# Microcontroller.net
KiCad netlist of a schematic drawn in Altium Designer
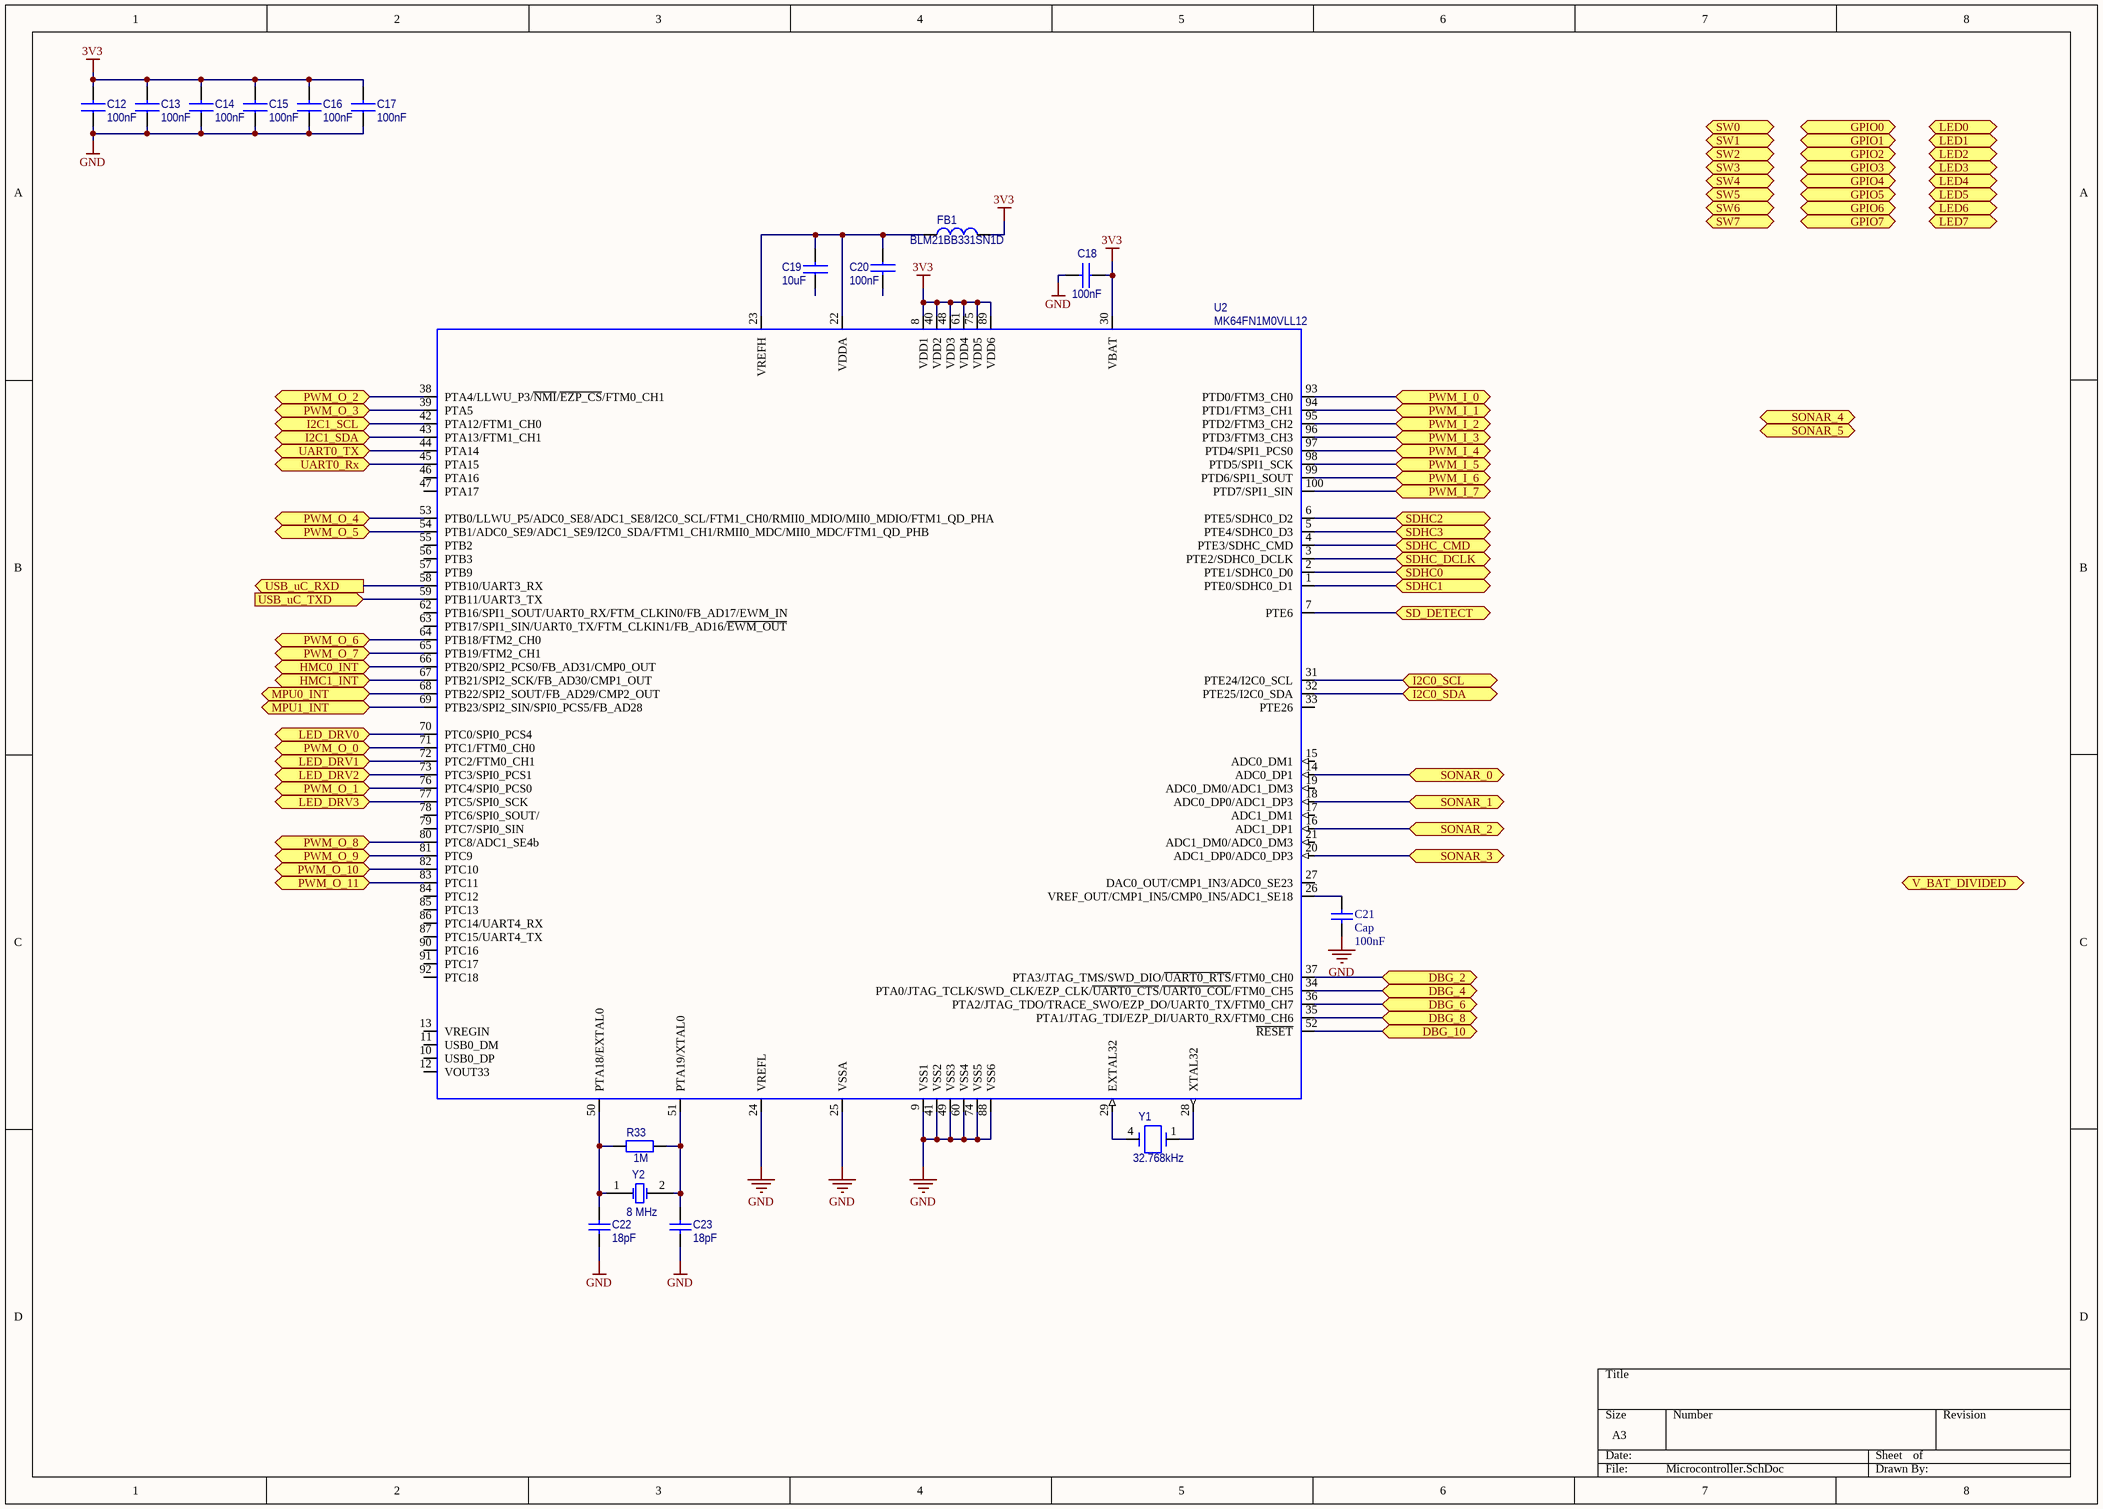
[diagram p0: Microcontroller.SchDoc]

(export (version "E")
  (design (tool "Eeschema 10.0.6"))
  (components
    (comp (ref "C12")
      (value "100nF")
      (footprint "060301")
      (description "CAP CER 0.1UF 25V 10% X7R 0603")
      (fields (field (name "VOLTAGE") "25V"))
      (libsource (lib "EISI") (part "CAPA"))
    )
    (comp (ref "C13")
      (value "100nF")
      (footprint "060301")
      (description "CAP CER 0.1UF 25V 10% X7R 0603")
      (fields (field (name "VOLTAGE") "25V"))
      (libsource (lib "EISI") (part "CAPA"))
    )
    (comp (ref "C14")
      (value "100nF")
      (footprint "060301")
      (description "CAP CER 0.1UF 25V 10% X7R 0603")
      (fields (field (name "VOLTAGE") "25V"))
      (libsource (lib "EISI") (part "CAPA"))
    )
    (comp (ref "C15")
      (value "100nF")
      (footprint "060301")
      (description "CAP CER 0.1UF 25V 10% X7R 0603")
      (fields (field (name "VOLTAGE") "25V"))
      (libsource (lib "EISI") (part "CAPA"))
    )
    (comp (ref "C16")
      (value "100nF")
      (footprint "060301")
      (description "CAP CER 0.1UF 25V 10% X7R 0603")
      (fields (field (name "VOLTAGE") "25V"))
      (libsource (lib "EISI") (part "CAPA"))
    )
    (comp (ref "C17")
      (value "100nF")
      (footprint "060301")
      (description "CAP CER 0.1UF 25V 10% X7R 0603")
      (fields (field (name "VOLTAGE") "25V"))
      (libsource (lib "EISI") (part "CAPA"))
    )
    (comp (ref "C18")
      (value "100nF")
      (footprint "060301")
      (description "CAP CER 0.1UF 25V 10% X7R 0603")
      (fields (field (name "VOLTAGE") "25V"))
      (libsource (lib "EISI") (part "CAPA"))
    )
    (comp (ref "C19")
      (value "10uF")
      (footprint "060301")
      (description "CAP CER 10UF 10V 10% X5R 0603")
      (fields (field (name "VOLTAGE") "10V") (field (name "Comment") "C1608X5R1A106K080AC"))
      (libsource (lib "EISI") (part "CAPA"))
    )
    (comp (ref "C20")
      (value "100nF")
      (footprint "060301")
      (description "CAP CER 0.1UF 25V 10% X7R 0603")
      (fields (field (name "VOLTAGE") "25V"))
      (libsource (lib "EISI") (part "CAPA"))
    )
    (comp (ref "C21")
      (value "Cap")
      (footprint "RAD-0.3")
      (description "Capacitor")
      (fields (field (name "ALTIUM_VALUE") "100nF") (field (name "PUBLISHER") "Altium Limited"))
      (libsource (lib "Miscellaneous Devices") (part "Cap"))
    )
    (comp (ref "C22")
      (value "18pF")
      (footprint "060301")
      (description "CAP CER 18PF 50V 5% NP0 0603")
      (libsource (lib "Miscellaneous Devices") (part "Cap Semi"))
    )
    (comp (ref "C23")
      (value "18pF")
      (footprint "060301")
      (description "CAP CER 18PF 50V 5% NP0 0603")
      (libsource (lib "Miscellaneous Devices") (part "Cap Semi"))
    )
    (comp (ref "FB1")
      (value "BLM21BB331SN1D")
      (footprint "080501")
      (description "EMI Filter Beads, Chips & Arrays 0805 330 OHM")
      (libsource (lib "EISI") (part "Ferrite Bead"))
    )
    (comp (ref "R33")
      (value "1M")
      (footprint "060301")
      (description "RES 1.00M OHM 1/10W 1% 0603 SMD")
      (libsource (lib "EISI") (part "RES"))
    )
    (comp (ref "U2")
      (value "MK64FN1M0VLL12")
      (description "IC MCU 1MB FLASH 120MHZ 1.71-3.6V LQFP100")
      (libsource (lib "SCH-28163-1") (part "K64FN1M0VLL12_100P"))
    )
    (comp (ref "Y1")
      (value "32.768kHz")
      (description "CRYSTAL 32.768 KHZ 12.5PF SMD")
      (fields (field (name "Comment") "ECS-.327-12.5-17X-C-TR"))
      (libsource (lib "*") (part "Crystal_32"))
    )
    (comp (ref "Y2")
      (value "8 MHz")
      (footprint "XT8_2-SMD")
      (description "CRYSTAL 8MHZ 18PF SMD")
      (fields (field (name "Comment") "ABM3-8.000MHZ-D2Y-T"))
      (libsource (lib "Miscellaneous Devices") (part "XTAL"))
    )
  )
  (nets
    (net (code "1") (name "/DBG_2") (class "Default")
      (node (ref "U2") (pin "37") (pinfunction "PTA3/JTAG_TMS/SWD_DIO/~{UART0_RTS}/FTM0_CH0_37") (pintype "bidirectional"))
    )
    (net (code "2") (name "/DBG_4") (class "Default")
      (node (ref "U2") (pin "34") (pinfunction "PTA0/JTAG_TCLK/SWD_CLK/EZP_CLK/~{UART0_CTS}/~{UART0_COL}/FTM0_CH5_34") (pintype "bidirectional"))
    )
    (net (code "3") (name "/DBG_6") (class "Default")
      (node (ref "U2") (pin "36") (pinfunction "PTA2/JTAG_TDO/TRACE_SWO/EZP_DO/UART0_TX/FTM0_CH7_36") (pintype "bidirectional"))
    )
    (net (code "4") (name "/DBG_8") (class "Default")
      (node (ref "U2") (pin "35") (pinfunction "PTA1/JTAG_TDI/EZP_DI/UART0_RX/FTM0_CH6_35") (pintype "bidirectional"))
    )
    (net (code "5") (name "/DBG_10") (class "Default")
      (node (ref "U2") (pin "52") (pinfunction "~{RESET}_52") (pintype "bidirectional"))
    )
    (net (code "14") (name "/HMC0_INT") (class "Default")
      (node (ref "U2") (pin "66") (pinfunction "PTB20/SPI2_PCS0/FB_AD31/CMP0_OUT_66") (pintype "bidirectional"))
    )
    (net (code "15") (name "/HMC1_INT") (class "Default")
      (node (ref "U2") (pin "67") (pinfunction "PTB21/SPI2_SCK/FB_AD30/CMP1_OUT_67") (pintype "bidirectional"))
    )
    (net (code "16") (name "/I2C0_SCL") (class "Default")
      (node (ref "U2") (pin "31") (pinfunction "PTE24/I2C0_SCL_31") (pintype "bidirectional"))
    )
    (net (code "17") (name "/I2C0_SDA") (class "Default")
      (node (ref "U2") (pin "32") (pinfunction "PTE25/I2C0_SDA_32") (pintype "bidirectional"))
    )
    (net (code "18") (name "/I2C1_SCL") (class "Default")
      (node (ref "U2") (pin "42") (pinfunction "PTA12/FTM1_CH0_42") (pintype "bidirectional"))
    )
    (net (code "19") (name "/I2C1_SDA") (class "Default")
      (node (ref "U2") (pin "43") (pinfunction "PTA13/FTM1_CH1_43") (pintype "bidirectional"))
    )
    (net (code "28") (name "/LED_DRV0") (class "Default")
      (node (ref "U2") (pin "70") (pinfunction "PTC0/SPI0_PCS4_70") (pintype "bidirectional"))
    )
    (net (code "29") (name "/LED_DRV1") (class "Default")
      (node (ref "U2") (pin "72") (pinfunction "PTC2/FTM0_CH1_72") (pintype "bidirectional"))
    )
    (net (code "30") (name "/LED_DRV2") (class "Default")
      (node (ref "U2") (pin "73") (pinfunction "PTC3/SPI0_PCS1_73") (pintype "bidirectional"))
    )
    (net (code "31") (name "/LED_DRV3") (class "Default")
      (node (ref "U2") (pin "77") (pinfunction "PTC5/SPI0_SCK_77") (pintype "bidirectional"))
    )
    (net (code "32") (name "/MPU0_INT") (class "Default")
      (node (ref "U2") (pin "68") (pinfunction "PTB22/SPI2_SOUT/FB_AD29/CMP2_OUT_68") (pintype "bidirectional"))
    )
    (net (code "33") (name "/MPU1_INT") (class "Default")
      (node (ref "U2") (pin "69") (pinfunction "PTB23/SPI2_SIN/SPI0_PCS5/FB_AD28_69") (pintype "bidirectional"))
    )
    (net (code "34") (name "/PWM_I_0") (class "Default")
      (node (ref "U2") (pin "93") (pinfunction "PTD0/FTM3_CH0_93") (pintype "bidirectional"))
    )
    (net (code "35") (name "/PWM_I_1") (class "Default")
      (node (ref "U2") (pin "94") (pinfunction "PTD1/FTM3_CH1_94") (pintype "bidirectional"))
    )
    (net (code "36") (name "/PWM_I_2") (class "Default")
      (node (ref "U2") (pin "95") (pinfunction "PTD2/FTM3_CH2_95") (pintype "bidirectional"))
    )
    (net (code "37") (name "/PWM_I_3") (class "Default")
      (node (ref "U2") (pin "96") (pinfunction "PTD3/FTM3_CH3_96") (pintype "bidirectional"))
    )
    (net (code "38") (name "/PWM_I_4") (class "Default")
      (node (ref "U2") (pin "97") (pinfunction "PTD4/SPI1_PCS0_97") (pintype "bidirectional"))
    )
    (net (code "39") (name "/PWM_I_5") (class "Default")
      (node (ref "U2") (pin "98") (pinfunction "PTD5/SPI1_SCK_98") (pintype "bidirectional"))
    )
    (net (code "40") (name "/PWM_I_6") (class "Default")
      (node (ref "U2") (pin "99") (pinfunction "PTD6/SPI1_SOUT_99") (pintype "bidirectional"))
    )
    (net (code "41") (name "/PWM_I_7") (class "Default")
      (node (ref "U2") (pin "100") (pinfunction "PTD7/SPI1_SIN_100") (pintype "bidirectional"))
    )
    (net (code "42") (name "/PWM_O_0") (class "Default")
      (node (ref "U2") (pin "71") (pinfunction "PTC1/FTM0_CH0_71") (pintype "bidirectional"))
    )
    (net (code "43") (name "/PWM_O_1") (class "Default")
      (node (ref "U2") (pin "76") (pinfunction "PTC4/SPI0_PCS0_76") (pintype "bidirectional"))
    )
    (net (code "44") (name "/PWM_O_2") (class "Default")
      (node (ref "U2") (pin "38") (pinfunction "PTA4/LLWU_P3/~{NMI}/~{EZP_CS}/FTM0_CH1_38") (pintype "bidirectional"))
    )
    (net (code "45") (name "/PWM_O_3") (class "Default")
      (node (ref "U2") (pin "39") (pinfunction "PTA5_39") (pintype "bidirectional"))
    )
    (net (code "46") (name "/PWM_O_4") (class "Default")
      (node (ref "U2") (pin "53") (pinfunction "PTB0/LLWU_P5/ADC0_SE8/ADC1_SE8/I2C0_SCL/FTM1_CH0/RMII0_MDIO/MII0_MDIO/FTM1_QD_PHA_53") (pintype "bidirectional"))
    )
    (net (code "47") (name "/PWM_O_5") (class "Default")
      (node (ref "U2") (pin "54") (pinfunction "PTB1/ADC0_SE9/ADC1_SE9/I2C0_SDA/FTM1_CH1/RMII0_MDC/MII0_MDC/FTM1_QD_PHB_54") (pintype "bidirectional"))
    )
    (net (code "48") (name "/PWM_O_6") (class "Default")
      (node (ref "U2") (pin "64") (pinfunction "PTB18/FTM2_CH0_64") (pintype "bidirectional"))
    )
    (net (code "49") (name "/PWM_O_7") (class "Default")
      (node (ref "U2") (pin "65") (pinfunction "PTB19/FTM2_CH1_65") (pintype "bidirectional"))
    )
    (net (code "50") (name "/PWM_O_8") (class "Default")
      (node (ref "U2") (pin "80") (pinfunction "PTC8/ADC1_SE4b_80") (pintype "bidirectional"))
    )
    (net (code "51") (name "/PWM_O_9") (class "Default")
      (node (ref "U2") (pin "81") (pinfunction "PTC9_81") (pintype "bidirectional"))
    )
    (net (code "52") (name "/PWM_O_10") (class "Default")
      (node (ref "U2") (pin "82") (pinfunction "PTC10_82") (pintype "bidirectional"))
    )
    (net (code "53") (name "/PWM_O_11") (class "Default")
      (node (ref "U2") (pin "83") (pinfunction "PTC11_83") (pintype "bidirectional"))
    )
    (net (code "54") (name "/SDHC0") (class "Default")
      (node (ref "U2") (pin "2") (pinfunction "PTE1/SDHC0_D0_2") (pintype "bidirectional"))
    )
    (net (code "55") (name "/SDHC1") (class "Default")
      (node (ref "U2") (pin "1") (pinfunction "PTE0/SDHC0_D1_1") (pintype "bidirectional"))
    )
    (net (code "56") (name "/SDHC2") (class "Default")
      (node (ref "U2") (pin "6") (pinfunction "PTE5/SDHC0_D2_6") (pintype "bidirectional"))
    )
    (net (code "57") (name "/SDHC3") (class "Default")
      (node (ref "U2") (pin "5") (pinfunction "PTE4/SDHC0_D3_5") (pintype "bidirectional"))
    )
    (net (code "58") (name "/SDHC_CMD") (class "Default")
      (node (ref "U2") (pin "4") (pinfunction "PTE3/SDHC_CMD_4") (pintype "bidirectional"))
    )
    (net (code "59") (name "/SDHC_DCLK") (class "Default")
      (node (ref "U2") (pin "3") (pinfunction "PTE2/SDHC0_DCLK_3") (pintype "bidirectional"))
    )
    (net (code "60") (name "/SD_DETECT") (class "Default")
      (node (ref "U2") (pin "7") (pinfunction "PTE6_7") (pintype "bidirectional"))
    )
    (net (code "61") (name "/SONAR_0") (class "Default")
      (node (ref "U2") (pin "14") (pinfunction "ADC0_DP1_14") (pintype "input"))
    )
    (net (code "62") (name "/SONAR_1") (class "Default")
      (node (ref "U2") (pin "18") (pinfunction "ADC0_DP0/ADC1_DP3_18") (pintype "input"))
    )
    (net (code "63") (name "/SONAR_2") (class "Default")
      (node (ref "U2") (pin "16") (pinfunction "ADC1_DP1_16") (pintype "input"))
    )
    (net (code "64") (name "/SONAR_3") (class "Default")
      (node (ref "U2") (pin "20") (pinfunction "ADC1_DP0/ADC0_DP3_20") (pintype "input"))
    )
    (net (code "75") (name "/UART0_Rx") (class "Default")
      (node (ref "U2") (pin "45") (pinfunction "PTA15_45") (pintype "bidirectional"))
    )
    (net (code "76") (name "/UART0_TX") (class "Default")
      (node (ref "U2") (pin "44") (pinfunction "PTA14_44") (pintype "bidirectional"))
    )
    (net (code "77") (name "/USB_uC_RXD") (class "Default")
      (node (ref "U2") (pin "58") (pinfunction "PTB10/UART3_RX_58") (pintype "bidirectional"))
    )
    (net (code "78") (name "/USB_uC_TXD") (class "Default")
      (node (ref "U2") (pin "59") (pinfunction "PTB11/UART3_TX_59") (pintype "bidirectional"))
    )
    (net (code "80") (name "3V3") (class "Default")
      (node (ref "C12") (pin "2") (pinfunction "2_2") (pintype "passive"))
      (node (ref "C13") (pin "2") (pinfunction "2_2") (pintype "passive"))
      (node (ref "C14") (pin "2") (pinfunction "2_2") (pintype "passive"))
      (node (ref "C15") (pin "2") (pinfunction "2_2") (pintype "passive"))
      (node (ref "C16") (pin "2") (pinfunction "2_2") (pintype "passive"))
      (node (ref "C17") (pin "2") (pinfunction "2_2") (pintype "passive"))
      (node (ref "C18") (pin "1") (pinfunction "1_1") (pintype "passive"))
      (node (ref "FB1") (pin "2") (pinfunction "2_2") (pintype "passive"))
      (node (ref "U2") (pin "30") (pinfunction "VBAT_30") (pintype "power_in"))
      (node (ref "U2") (pin "40") (pinfunction "VDD2_40") (pintype "power_in"))
      (node (ref "U2") (pin "48") (pinfunction "VDD3_48") (pintype "power_in"))
      (node (ref "U2") (pin "61") (pinfunction "VDD4_61") (pintype "power_in"))
      (node (ref "U2") (pin "75") (pinfunction "VDD5_75") (pintype "power_in"))
      (node (ref "U2") (pin "8") (pinfunction "VDD1_8") (pintype "power_in"))
      (node (ref "U2") (pin "89") (pinfunction "VDD6_89") (pintype "power_in"))
    )
    (net (code "81") (name "GND") (class "Default")
      (node (ref "C12") (pin "1") (pinfunction "1_1") (pintype "passive"))
      (node (ref "C13") (pin "1") (pinfunction "1_1") (pintype "passive"))
      (node (ref "C14") (pin "1") (pinfunction "1_1") (pintype "passive"))
      (node (ref "C15") (pin "1") (pinfunction "1_1") (pintype "passive"))
      (node (ref "C16") (pin "1") (pinfunction "1_1") (pintype "passive"))
      (node (ref "C17") (pin "1") (pinfunction "1_1") (pintype "passive"))
      (node (ref "C18") (pin "2") (pinfunction "2_2") (pintype "passive"))
      (node (ref "C21") (pin "1") (pinfunction "1_1") (pintype "passive"))
      (node (ref "C22") (pin "1") (pinfunction "1_1") (pintype "passive"))
      (node (ref "C23") (pin "1") (pinfunction "1_1") (pintype "passive"))
      (node (ref "U2") (pin "24") (pinfunction "VREFL_24") (pintype "power_in"))
      (node (ref "U2") (pin "25") (pinfunction "VSSA_25") (pintype "power_in"))
      (node (ref "U2") (pin "41") (pinfunction "VSS2_41") (pintype "power_in"))
      (node (ref "U2") (pin "49") (pinfunction "VSS3_49") (pintype "power_in"))
      (node (ref "U2") (pin "60") (pinfunction "VSS4_60") (pintype "power_in"))
      (node (ref "U2") (pin "74") (pinfunction "VSS5_74") (pintype "power_in"))
      (node (ref "U2") (pin "88") (pinfunction "VSS6_88") (pintype "power_in"))
      (node (ref "U2") (pin "9") (pinfunction "VSS1_9") (pintype "power_in"))
    )
    (net (code "82") (name "Net-(U2-EXTAL32)") (class "Default")
      (node (ref "U2") (pin "29") (pinfunction "EXTAL32_29") (pintype "input"))
      (node (ref "Y1") (pin "4") (pinfunction "4_4") (pintype "passive"))
    )
    (net (code "83") (name "Net-(U2-PTA18{slash}EXTAL0)") (class "Default")
      (node (ref "C22") (pin "2") (pinfunction "2_2") (pintype "passive"))
      (node (ref "R33") (pin "1") (pinfunction "1_1") (pintype "passive"))
      (node (ref "U2") (pin "50") (pinfunction "PTA18/EXTAL0_50") (pintype "bidirectional"))
      (node (ref "Y2") (pin "1") (pinfunction "OSC1_1") (pintype "passive"))
    )
    (net (code "84") (name "Net-(U2-PTA19{slash}XTAL0)") (class "Default")
      (node (ref "C23") (pin "2") (pinfunction "2_2") (pintype "passive"))
      (node (ref "R33") (pin "2") (pinfunction "2_2") (pintype "passive"))
      (node (ref "U2") (pin "51") (pinfunction "PTA19/XTAL0_51") (pintype "bidirectional"))
      (node (ref "Y2") (pin "2") (pinfunction "OSC2_2") (pintype "passive"))
    )
    (net (code "85") (name "Net-(U2-VDDA)") (class "Default")
      (node (ref "C19") (pin "2") (pinfunction "2_2") (pintype "passive"))
      (node (ref "C20") (pin "1") (pinfunction "1_1") (pintype "passive"))
      (node (ref "FB1") (pin "1") (pinfunction "1_1") (pintype "passive"))
      (node (ref "U2") (pin "22") (pinfunction "VDDA_22") (pintype "power_in"))
      (node (ref "U2") (pin "23") (pinfunction "VREFH_23") (pintype "power_in"))
    )
    (net (code "86") (name "Net-(U2-VREF_OUT{slash}CMP1_IN5{slash}CMP0_IN5{slash}ADC1_SE18)") (class "Default")
      (node (ref "C21") (pin "2") (pinfunction "2_2") (pintype "passive"))
      (node (ref "U2") (pin "26") (pinfunction "VREF_OUT/CMP1_IN5/CMP0_IN5/ADC1_SE18_26") (pintype "bidirectional"))
    )
    (net (code "87") (name "Net-(U2-XTAL32)") (class "Default")
      (node (ref "U2") (pin "28") (pinfunction "XTAL32_28") (pintype "output"))
      (node (ref "Y1") (pin "1") (pinfunction "1_1") (pintype "passive"))
    )
    (net (code "88") (name "unconnected-(C19-Pad1)") (class "Default")
      (node (ref "C19") (pin "1") (pinfunction "1_1") (pintype "passive"))
    )
    (net (code "89") (name "unconnected-(C20-Pad2)") (class "Default")
      (node (ref "C20") (pin "2") (pinfunction "2_2") (pintype "passive"))
    )
    (net (code "90") (name "unconnected-(U2-ADC0_DM0{slash}ADC1_DM3-Pad19)") (class "Default")
      (node (ref "U2") (pin "19") (pinfunction "ADC0_DM0/ADC1_DM3_19") (pintype "input"))
    )
    (net (code "91") (name "unconnected-(U2-ADC0_DM1-Pad15)") (class "Default")
      (node (ref "U2") (pin "15") (pinfunction "ADC0_DM1_15") (pintype "input"))
    )
    (net (code "92") (name "unconnected-(U2-ADC1_DM0{slash}ADC0_DM3-Pad21)") (class "Default")
      (node (ref "U2") (pin "21") (pinfunction "ADC1_DM0/ADC0_DM3_21") (pintype "input"))
    )
    (net (code "93") (name "unconnected-(U2-ADC1_DM1-Pad17)") (class "Default")
      (node (ref "U2") (pin "17") (pinfunction "ADC1_DM1_17") (pintype "input"))
    )
    (net (code "94") (name "unconnected-(U2-DAC0_OUT{slash}CMP1_IN3{slash}ADC0_SE23-Pad27)") (class "Default")
      (node (ref "U2") (pin "27") (pinfunction "DAC0_OUT/CMP1_IN3/ADC0_SE23_27") (pintype "bidirectional"))
    )
    (net (code "95") (name "unconnected-(U2-PTA16-Pad46)") (class "Default")
      (node (ref "U2") (pin "46") (pinfunction "PTA16_46") (pintype "bidirectional"))
    )
    (net (code "96") (name "unconnected-(U2-PTA17-Pad47)") (class "Default")
      (node (ref "U2") (pin "47") (pinfunction "PTA17_47") (pintype "bidirectional"))
    )
    (net (code "97") (name "unconnected-(U2-PTB2-Pad55)") (class "Default")
      (node (ref "U2") (pin "55") (pinfunction "PTB2_55") (pintype "bidirectional"))
    )
    (net (code "98") (name "unconnected-(U2-PTB3-Pad56)") (class "Default")
      (node (ref "U2") (pin "56") (pinfunction "PTB3_56") (pintype "bidirectional"))
    )
    (net (code "99") (name "unconnected-(U2-PTB9-Pad57)") (class "Default")
      (node (ref "U2") (pin "57") (pinfunction "PTB9_57") (pintype "bidirectional"))
    )
    (net (code "100") (name "unconnected-(U2-PTB16{slash}SPI1_SOUT{slash}UART0_RX{slash}FTM_CLKIN0{slash}FB_AD17{slash}EWM_IN-Pad62)") (class "Default")
      (node (ref "U2") (pin "62") (pinfunction "PTB16/SPI1_SOUT/UART0_RX/FTM_CLKIN0/FB_AD17/EWM_IN_62") (pintype "bidirectional"))
    )
    (net (code "101") (name "unconnected-(U2-PTB17{slash}SPI1_SIN{slash}UART0_TX{slash}FTM_CLKIN1{slash}FB_AD16{slash}~{EWM_OUT}-Pad63)") (class "Default")
      (node (ref "U2") (pin "63") (pinfunction "PTB17/SPI1_SIN/UART0_TX/FTM_CLKIN1/FB_AD16/~{EWM_OUT}_63") (pintype "bidirectional"))
    )
    (net (code "102") (name "unconnected-(U2-PTC6{slash}SPI0_SOUT{slash}-Pad78)") (class "Default")
      (node (ref "U2") (pin "78") (pinfunction "PTC6/SPI0_SOUT/_78") (pintype "bidirectional"))
    )
    (net (code "103") (name "unconnected-(U2-PTC7{slash}SPI0_SIN-Pad79)") (class "Default")
      (node (ref "U2") (pin "79") (pinfunction "PTC7/SPI0_SIN_79") (pintype "bidirectional"))
    )
    (net (code "104") (name "unconnected-(U2-PTC12-Pad84)") (class "Default")
      (node (ref "U2") (pin "84") (pinfunction "PTC12_84") (pintype "bidirectional"))
    )
    (net (code "105") (name "unconnected-(U2-PTC13-Pad85)") (class "Default")
      (node (ref "U2") (pin "85") (pinfunction "PTC13_85") (pintype "bidirectional"))
    )
    (net (code "106") (name "unconnected-(U2-PTC14{slash}UART4_RX-Pad86)") (class "Default")
      (node (ref "U2") (pin "86") (pinfunction "PTC14/UART4_RX_86") (pintype "bidirectional"))
    )
    (net (code "107") (name "unconnected-(U2-PTC15{slash}UART4_TX-Pad87)") (class "Default")
      (node (ref "U2") (pin "87") (pinfunction "PTC15/UART4_TX_87") (pintype "bidirectional"))
    )
    (net (code "108") (name "unconnected-(U2-PTC16-Pad90)") (class "Default")
      (node (ref "U2") (pin "90") (pinfunction "PTC16_90") (pintype "bidirectional"))
    )
    (net (code "109") (name "unconnected-(U2-PTC17-Pad91)") (class "Default")
      (node (ref "U2") (pin "91") (pinfunction "PTC17_91") (pintype "bidirectional"))
    )
    (net (code "110") (name "unconnected-(U2-PTC18-Pad92)") (class "Default")
      (node (ref "U2") (pin "92") (pinfunction "PTC18_92") (pintype "bidirectional"))
    )
    (net (code "111") (name "unconnected-(U2-PTE26-Pad33)") (class "Default")
      (node (ref "U2") (pin "33") (pinfunction "PTE26_33") (pintype "bidirectional"))
    )
    (net (code "112") (name "unconnected-(U2-USB0_DM-Pad11)") (class "Default")
      (node (ref "U2") (pin "11") (pinfunction "USB0_DM_11") (pintype "bidirectional"))
    )
    (net (code "113") (name "unconnected-(U2-USB0_DP-Pad10)") (class "Default")
      (node (ref "U2") (pin "10") (pinfunction "USB0_DP_10") (pintype "bidirectional"))
    )
    (net (code "114") (name "unconnected-(U2-VOUT33-Pad12)") (class "Default")
      (node (ref "U2") (pin "12") (pinfunction "VOUT33_12") (pintype "power_in"))
    )
    (net (code "115") (name "unconnected-(U2-VREGIN-Pad13)") (class "Default")
      (node (ref "U2") (pin "13") (pinfunction "VREGIN_13") (pintype "power_in"))
    )
  )
)
